# PIC_16F877A_Board_V2.net
KiCad netlist of a schematic drawn in EAGLE
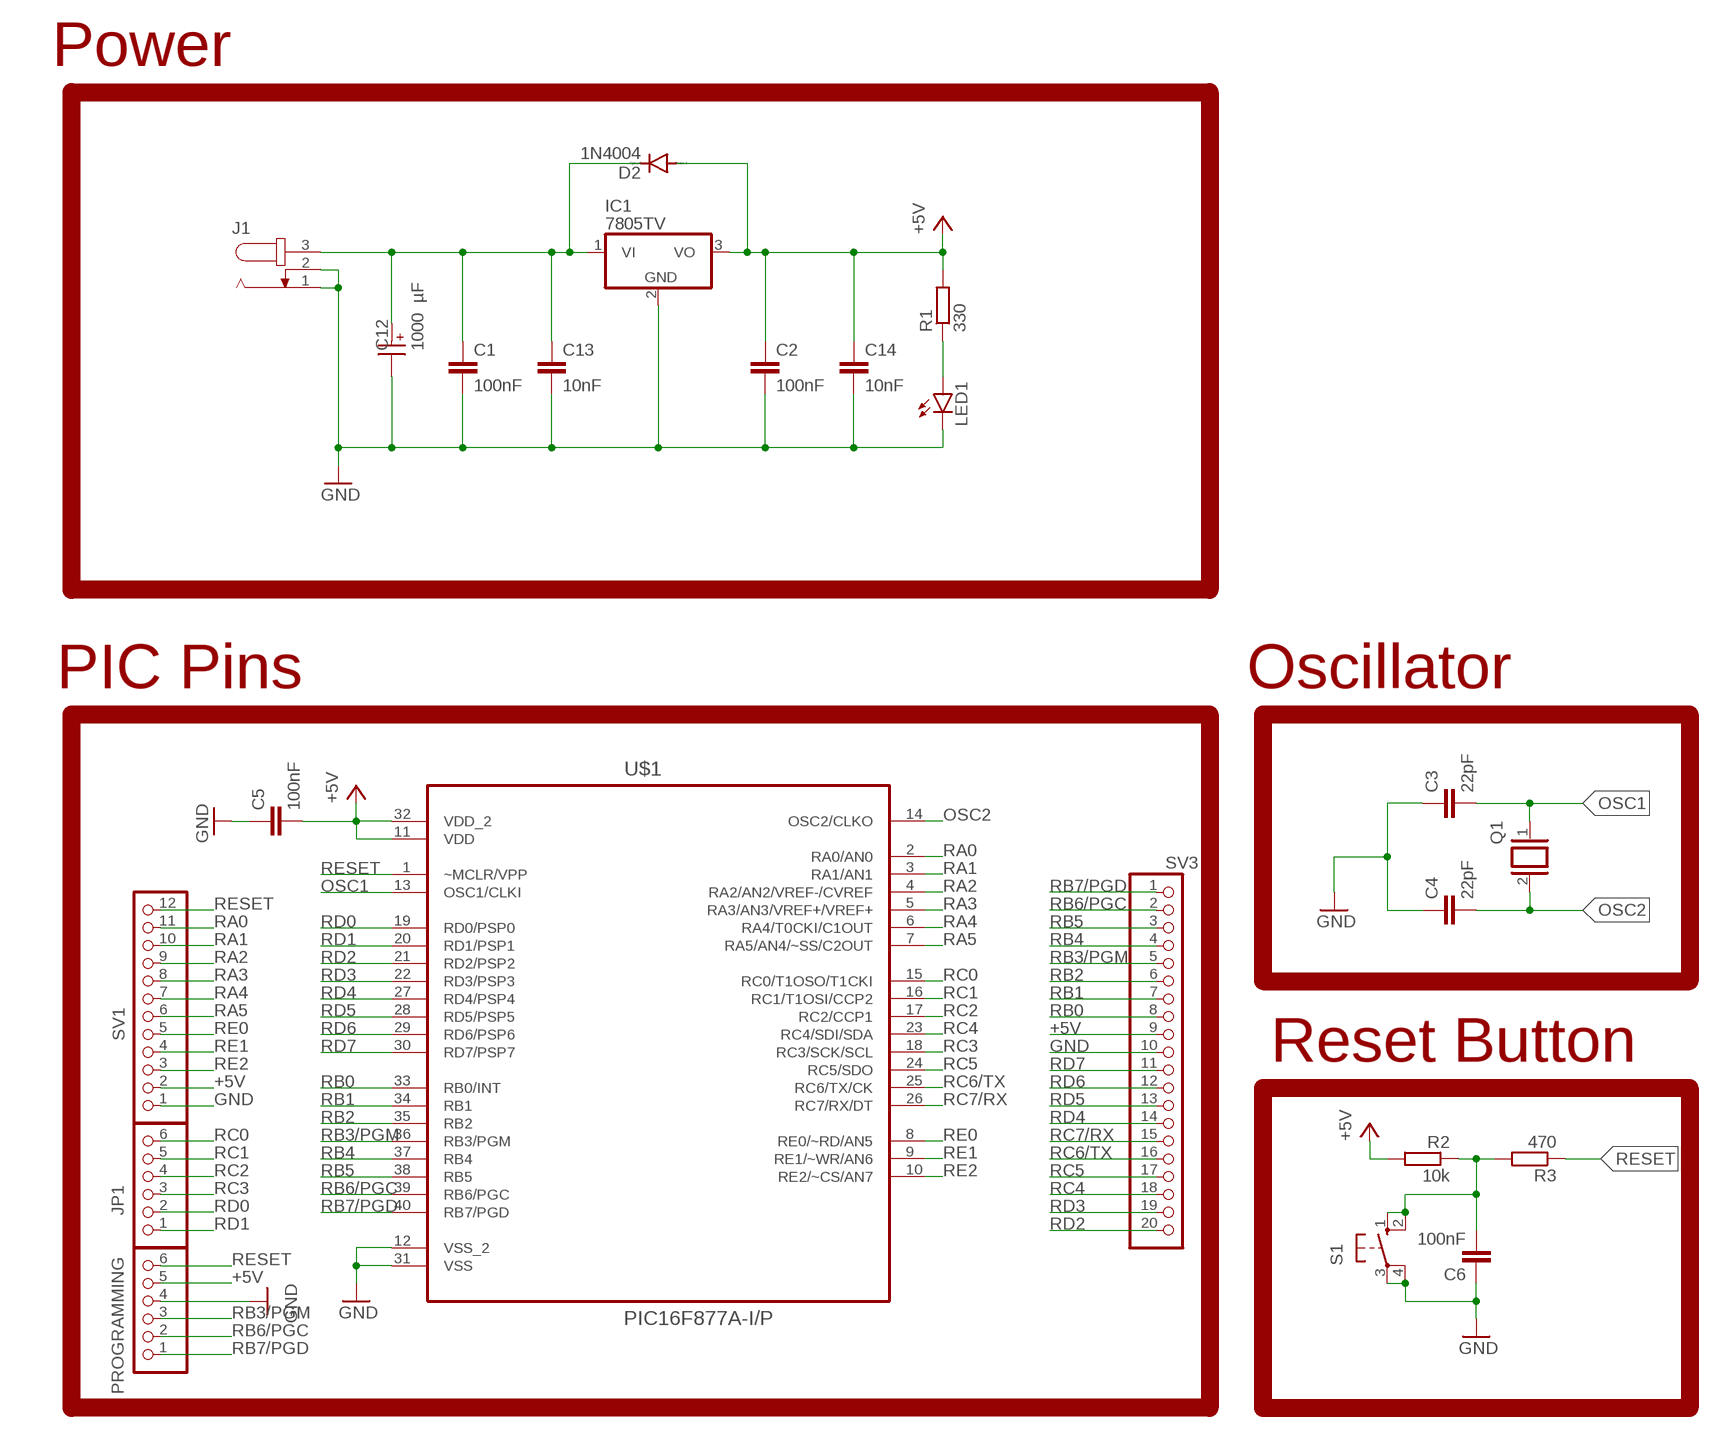
[diagram p0: schematic, sheet 1]

(export (version "E")
  (design (tool "Eeschema 10.0.6"))
  (components
    (comp (ref "C1")
      (value "100nF")
      (footprint "eagle-import:C025-025X050")
      (libsource (lib "eagle-import") (part "C-EU025-025X050"))
    )
    (comp (ref "C2")
      (value "100nF")
      (footprint "eagle-import:C025-025X050")
      (libsource (lib "eagle-import") (part "C-EU025-025X050"))
    )
    (comp (ref "C3")
      (value "22pF")
      (footprint "eagle-import:C025-025X050")
      (libsource (lib "eagle-import") (part "C-EU025-025X050"))
    )
    (comp (ref "C4")
      (value "22pF")
      (footprint "eagle-import:C025-025X050")
      (libsource (lib "eagle-import") (part "C-EU025-025X050"))
    )
    (comp (ref "C5")
      (value "100nF")
      (footprint "eagle-import:C025-025X050")
      (libsource (lib "eagle-import") (part "C-EU025-025X050"))
    )
    (comp (ref "C6")
      (value "100nF")
      (footprint "eagle-import:C025-025X050")
      (libsource (lib "eagle-import") (part "C-EU025-025X050"))
    )
    (comp (ref "C12")
      (value "1000 µF")
      (footprint "eagle-import:WCAP-ATG8_10X12.5(DXL)")
      (libsource (lib "eagle-import") (part "WCAP-ATG8_10X12.5_860010275016"))
    )
    (comp (ref "C13")
      (value "10nF")
      (footprint "eagle-import:C025-025X050")
      (libsource (lib "eagle-import") (part "C-EU025-025X050"))
    )
    (comp (ref "C14")
      (value "10nF")
      (footprint "eagle-import:C025-025X050")
      (libsource (lib "eagle-import") (part "C-EU025-025X050"))
    )
    (comp (ref "D2")
      (value "1N4004")
      (footprint "eagle-import:DO41-10")
      (libsource (lib "eagle-import") (part "1N4004"))
    )
    (comp (ref "IC1")
      (value "7805TV")
      (footprint "eagle-import:TO220V")
      (libsource (lib "eagle-import") (part "78TV05"))
    )
    (comp (ref "J1")
      (value "JACK-PLUG0")
      (footprint "eagle-import:SPC4077")
      (libsource (lib "eagle-import") (part "JACK-PLUG0"))
    )
    (comp (ref "JP1")
      (value "PINHD-1X6")
      (footprint "eagle-import:1X06")
      (libsource (lib "eagle-import") (part "PINHD-1X6"))
    )
    (comp (ref "LED1")
      (value "LED3MM")
      (footprint "eagle-import:LED3MM")
      (libsource (lib "eagle-import") (part "LED3MM"))
    )
    (comp (ref "PROGRAMMING")
      (value "PINHD-1X6")
      (footprint "eagle-import:1X06")
      (libsource (lib "eagle-import") (part "PINHD-1X6"))
    )
    (comp (ref "Q1")
      (value "XTAL/S")
      (footprint "eagle-import:QS")
      (libsource (lib "eagle-import") (part "XTAL/S"))
    )
    (comp (ref "R1")
      (value "330")
      (footprint "eagle-import:0204_7")
      (libsource (lib "eagle-import") (part "R-EU_0204/7"))
    )
    (comp (ref "R2")
      (value "10k")
      (footprint "eagle-import:0204_7")
      (libsource (lib "eagle-import") (part "R-EU_0204/7"))
    )
    (comp (ref "R3")
      (value "470")
      (footprint "eagle-import:0204_7")
      (libsource (lib "eagle-import") (part "R-EU_0204/7"))
    )
    (comp (ref "S1")
      (value "10-XX")
      (footprint "eagle-import:B3F-10XX")
      (fields (field (name "MPN") "B3F-1000"))
      (libsource (lib "eagle-import") (part "10-XX"))
    )
    (comp (ref "SV1")
      (value "PINHD-1X12")
      (footprint "eagle-import:1X12")
      (libsource (lib "eagle-import") (part "PINHD-1X12"))
    )
    (comp (ref "SV3")
      (value "PINHD-1X20")
      (footprint "eagle-import:1X20")
      (libsource (lib "eagle-import") (part "PINHD-1X20"))
    )
    (comp (ref "U$1")
      (value "PIC16F877A-I/P")
      (footprint "eagle-import:16F877A")
      (fields (field (name "MF") "Microchip"))
      (libsource (lib "eagle-import") (part "PIC16F877A-I/P"))
    )
  )
  (nets
    (net (code "1") (name "+5V") (class "Default")
      (node (ref "C14") (pin "1") (pinfunction "1_1") (pintype "passive"))
      (node (ref "C2") (pin "1") (pinfunction "1_1") (pintype "passive"))
      (node (ref "C5") (pin "2") (pinfunction "2_2") (pintype "passive"))
      (node (ref "D2") (pin "A") (pinfunction "A_A") (pintype "passive"))
      (node (ref "IC1") (pin "3") (pinfunction "VO_3") (pintype "passive"))
      (node (ref "PROGRAMMING") (pin "5") (pinfunction "5_5") (pintype "passive"))
      (node (ref "R1") (pin "2") (pinfunction "2_2") (pintype "passive"))
      (node (ref "R2") (pin "2") (pinfunction "2_2") (pintype "passive"))
      (node (ref "SV1") (pin "2") (pinfunction "2_2") (pintype "passive"))
      (node (ref "SV3") (pin "9") (pinfunction "9_9") (pintype "passive"))
      (node (ref "U$1") (pin "11") (pinfunction "VDD_11") (pintype "power_in"))
      (node (ref "U$1") (pin "32") (pinfunction "VDD_2_32") (pintype "power_in"))
    )
    (net (code "2") (name "/RA0") (class "Default")
      (node (ref "SV1") (pin "11") (pinfunction "11_11") (pintype "passive"))
      (node (ref "U$1") (pin "2") (pinfunction "RA0/AN0_2") (pintype "bidirectional"))
    )
    (net (code "3") (name "/RA1") (class "Default")
      (node (ref "SV1") (pin "10") (pinfunction "10_10") (pintype "passive"))
      (node (ref "U$1") (pin "3") (pinfunction "RA1/AN1_3") (pintype "bidirectional"))
    )
    (net (code "4") (name "/RA2") (class "Default")
      (node (ref "SV1") (pin "9") (pinfunction "9_9") (pintype "passive"))
      (node (ref "U$1") (pin "4") (pinfunction "RA2/AN2/VREF-/CVREF_4") (pintype "bidirectional"))
    )
    (net (code "5") (name "/RA3") (class "Default")
      (node (ref "SV1") (pin "8") (pinfunction "8_8") (pintype "passive"))
      (node (ref "U$1") (pin "5") (pinfunction "RA3/AN3/VREF+/VREF+_5") (pintype "bidirectional"))
    )
    (net (code "6") (name "/RA4") (class "Default")
      (node (ref "SV1") (pin "7") (pinfunction "7_7") (pintype "passive"))
      (node (ref "U$1") (pin "6") (pinfunction "RA4/T0CKI/C1OUT_6") (pintype "bidirectional"))
    )
    (net (code "7") (name "/RA5") (class "Default")
      (node (ref "SV1") (pin "6") (pinfunction "6_6") (pintype "passive"))
      (node (ref "U$1") (pin "7") (pinfunction "RA5/AN4/~{SS/C2OUT}_7") (pintype "bidirectional"))
    )
    (net (code "8") (name "/RB0") (class "Default")
      (node (ref "SV3") (pin "8") (pinfunction "8_8") (pintype "passive"))
      (node (ref "U$1") (pin "33") (pinfunction "RB0/INT_33") (pintype "bidirectional"))
    )
    (net (code "9") (name "/RB1") (class "Default")
      (node (ref "SV3") (pin "7") (pinfunction "7_7") (pintype "passive"))
      (node (ref "U$1") (pin "34") (pinfunction "RB1_34") (pintype "bidirectional"))
    )
    (net (code "10") (name "/RB2") (class "Default")
      (node (ref "SV3") (pin "6") (pinfunction "6_6") (pintype "passive"))
      (node (ref "U$1") (pin "35") (pinfunction "RB2_35") (pintype "bidirectional"))
    )
    (net (code "11") (name "/RB3{slash}PGM") (class "Default")
      (node (ref "PROGRAMMING") (pin "3") (pinfunction "3_3") (pintype "passive"))
      (node (ref "SV3") (pin "5") (pinfunction "5_5") (pintype "passive"))
      (node (ref "U$1") (pin "36") (pinfunction "RB3/PGM_36") (pintype "bidirectional"))
    )
    (net (code "12") (name "/RB4") (class "Default")
      (node (ref "SV3") (pin "4") (pinfunction "4_4") (pintype "passive"))
      (node (ref "U$1") (pin "37") (pinfunction "RB4_37") (pintype "bidirectional"))
    )
    (net (code "13") (name "/RB5") (class "Default")
      (node (ref "SV3") (pin "3") (pinfunction "3_3") (pintype "passive"))
      (node (ref "U$1") (pin "38") (pinfunction "RB5_38") (pintype "bidirectional"))
    )
    (net (code "14") (name "/RB6{slash}PGC") (class "Default")
      (node (ref "PROGRAMMING") (pin "2") (pinfunction "2_2") (pintype "passive"))
      (node (ref "SV3") (pin "2") (pinfunction "2_2") (pintype "passive"))
      (node (ref "U$1") (pin "39") (pinfunction "RB6/PGC_39") (pintype "bidirectional"))
    )
    (net (code "15") (name "/RB7{slash}PGD") (class "Default")
      (node (ref "PROGRAMMING") (pin "1") (pinfunction "1_1") (pintype "passive"))
      (node (ref "SV3") (pin "1") (pinfunction "1_1") (pintype "passive"))
      (node (ref "U$1") (pin "40") (pinfunction "RB7/PGD_40") (pintype "bidirectional"))
    )
    (net (code "16") (name "/RC0") (class "Default")
      (node (ref "JP1") (pin "6") (pinfunction "6_6") (pintype "passive"))
      (node (ref "U$1") (pin "15") (pinfunction "RC0/T1OSO/T1CKI_15") (pintype "bidirectional"))
    )
    (net (code "17") (name "/RC1") (class "Default")
      (node (ref "JP1") (pin "5") (pinfunction "5_5") (pintype "passive"))
      (node (ref "U$1") (pin "16") (pinfunction "RC1/T1OSI/CCP2_16") (pintype "bidirectional"))
    )
    (net (code "18") (name "/RC2") (class "Default")
      (node (ref "JP1") (pin "4") (pinfunction "4_4") (pintype "passive"))
      (node (ref "U$1") (pin "17") (pinfunction "RC2/CCP1_17") (pintype "bidirectional"))
    )
    (net (code "19") (name "/RC3") (class "Default")
      (node (ref "JP1") (pin "3") (pinfunction "3_3") (pintype "passive"))
      (node (ref "U$1") (pin "18") (pinfunction "RC3/SCK/SCL_18") (pintype "bidirectional"))
    )
    (net (code "20") (name "/RC4") (class "Default")
      (node (ref "SV3") (pin "18") (pinfunction "18_18") (pintype "passive"))
      (node (ref "U$1") (pin "23") (pinfunction "RC4/SDI/SDA_23") (pintype "bidirectional"))
    )
    (net (code "21") (name "/RC5") (class "Default")
      (node (ref "SV3") (pin "17") (pinfunction "17_17") (pintype "passive"))
      (node (ref "U$1") (pin "24") (pinfunction "RC5/SDO_24") (pintype "bidirectional"))
    )
    (net (code "22") (name "/RC6{slash}TX") (class "Default")
      (node (ref "SV3") (pin "16") (pinfunction "16_16") (pintype "passive"))
      (node (ref "U$1") (pin "25") (pinfunction "RC6/TX/CK_25") (pintype "bidirectional"))
    )
    (net (code "23") (name "/RC7{slash}RX") (class "Default")
      (node (ref "SV3") (pin "15") (pinfunction "15_15") (pintype "passive"))
      (node (ref "U$1") (pin "26") (pinfunction "RC7/RX/DT_26") (pintype "bidirectional"))
    )
    (net (code "24") (name "/RD0") (class "Default")
      (node (ref "JP1") (pin "2") (pinfunction "2_2") (pintype "passive"))
      (node (ref "U$1") (pin "19") (pinfunction "RD0/PSP0_19") (pintype "bidirectional"))
    )
    (net (code "25") (name "/RD1") (class "Default")
      (node (ref "JP1") (pin "1") (pinfunction "1_1") (pintype "passive"))
      (node (ref "U$1") (pin "20") (pinfunction "RD1/PSP1_20") (pintype "bidirectional"))
    )
    (net (code "26") (name "/RD2") (class "Default")
      (node (ref "SV3") (pin "20") (pinfunction "20_20") (pintype "passive"))
      (node (ref "U$1") (pin "21") (pinfunction "RD2/PSP2_21") (pintype "bidirectional"))
    )
    (net (code "27") (name "/RD3") (class "Default")
      (node (ref "SV3") (pin "19") (pinfunction "19_19") (pintype "passive"))
      (node (ref "U$1") (pin "22") (pinfunction "RD3/PSP3_22") (pintype "bidirectional"))
    )
    (net (code "28") (name "/RD4") (class "Default")
      (node (ref "SV3") (pin "14") (pinfunction "14_14") (pintype "passive"))
      (node (ref "U$1") (pin "27") (pinfunction "RD4/PSP4_27") (pintype "bidirectional"))
    )
    (net (code "29") (name "/RD5") (class "Default")
      (node (ref "SV3") (pin "13") (pinfunction "13_13") (pintype "passive"))
      (node (ref "U$1") (pin "28") (pinfunction "RD5/PSP5_28") (pintype "bidirectional"))
    )
    (net (code "30") (name "/RD6") (class "Default")
      (node (ref "SV3") (pin "12") (pinfunction "12_12") (pintype "passive"))
      (node (ref "U$1") (pin "29") (pinfunction "RD6/PSP6_29") (pintype "bidirectional"))
    )
    (net (code "31") (name "/RD7") (class "Default")
      (node (ref "SV3") (pin "11") (pinfunction "11_11") (pintype "passive"))
      (node (ref "U$1") (pin "30") (pinfunction "RD7/PSP7_30") (pintype "bidirectional"))
    )
    (net (code "32") (name "/RE0") (class "Default")
      (node (ref "SV1") (pin "5") (pinfunction "5_5") (pintype "passive"))
      (node (ref "U$1") (pin "8") (pinfunction "RE0/~{RD/AN5}_8") (pintype "bidirectional"))
    )
    (net (code "33") (name "/RE1") (class "Default")
      (node (ref "SV1") (pin "4") (pinfunction "4_4") (pintype "passive"))
      (node (ref "U$1") (pin "9") (pinfunction "RE1/~{WR/AN6}_9") (pintype "bidirectional"))
    )
    (net (code "34") (name "/RE2") (class "Default")
      (node (ref "SV1") (pin "3") (pinfunction "3_3") (pintype "passive"))
      (node (ref "U$1") (pin "10") (pinfunction "RE2/~{CS/AN7}_10") (pintype "bidirectional"))
    )
    (net (code "35") (name "GND") (class "Default")
      (node (ref "C1") (pin "2") (pinfunction "2_2") (pintype "passive"))
      (node (ref "C12") (pin "2") (pinfunction "-_2") (pintype "passive"))
      (node (ref "C13") (pin "2") (pinfunction "2_2") (pintype "passive"))
      (node (ref "C14") (pin "2") (pinfunction "2_2") (pintype "passive"))
      (node (ref "C2") (pin "2") (pinfunction "2_2") (pintype "passive"))
      (node (ref "C3") (pin "1") (pinfunction "1_1") (pintype "passive"))
      (node (ref "C4") (pin "1") (pinfunction "1_1") (pintype "passive"))
      (node (ref "C5") (pin "1") (pinfunction "1_1") (pintype "passive"))
      (node (ref "C6") (pin "1") (pinfunction "1_1") (pintype "passive"))
      (node (ref "IC1") (pin "2") (pinfunction "GND_2") (pintype "passive"))
      (node (ref "J1") (pin "1") (pinfunction "1_1") (pintype "passive"))
      (node (ref "J1") (pin "2") (pinfunction "2_2") (pintype "passive"))
      (node (ref "LED1") (pin "K") (pinfunction "C_K") (pintype "passive"))
      (node (ref "PROGRAMMING") (pin "4") (pinfunction "4_4") (pintype "passive"))
      (node (ref "S1") (pin "3") (pinfunction "P_3") (pintype "passive"))
      (node (ref "S1") (pin "4") (pinfunction "P1_4") (pintype "passive"))
      (node (ref "SV1") (pin "1") (pinfunction "1_1") (pintype "passive"))
      (node (ref "SV3") (pin "10") (pinfunction "10_10") (pintype "passive"))
      (node (ref "U$1") (pin "12") (pinfunction "VSS_2_12") (pintype "power_in"))
      (node (ref "U$1") (pin "31") (pinfunction "VSS_31") (pintype "power_in"))
    )
    (net (code "36") (name "Net-(C12-+)") (class "Default")
      (node (ref "C1") (pin "1") (pinfunction "1_1") (pintype "passive"))
      (node (ref "C12") (pin "1") (pinfunction "+_1") (pintype "passive"))
      (node (ref "C13") (pin "1") (pinfunction "1_1") (pintype "passive"))
      (node (ref "D2") (pin "C") (pinfunction "C_C") (pintype "passive"))
      (node (ref "IC1") (pin "1") (pinfunction "VI_1") (pintype "input"))
      (node (ref "J1") (pin "3") (pinfunction "3_3") (pintype "passive"))
    )
    (net (code "37") (name "Net-(LED1-PadA)") (class "Default")
      (node (ref "LED1") (pin "A") (pinfunction "A_A") (pintype "passive"))
      (node (ref "R1") (pin "1") (pinfunction "1_1") (pintype "passive"))
    )
    (net (code "38") (name "Net-(S1-S)") (class "Default")
      (node (ref "C6") (pin "2") (pinfunction "2_2") (pintype "passive"))
      (node (ref "R2") (pin "1") (pinfunction "1_1") (pintype "passive"))
      (node (ref "R3") (pin "2") (pinfunction "2_2") (pintype "passive"))
      (node (ref "S1") (pin "1") (pinfunction "S_1") (pintype "passive"))
      (node (ref "S1") (pin "2") (pinfunction "S1_2") (pintype "passive"))
    )
    (net (code "39") (name "OSC1") (class "Default")
      (node (ref "C3") (pin "2") (pinfunction "2_2") (pintype "passive"))
      (node (ref "Q1") (pin "1") (pinfunction "1_1") (pintype "passive"))
      (node (ref "U$1") (pin "13") (pinfunction "OSC1/CLKI_13") (pintype "input"))
    )
    (net (code "40") (name "OSC2") (class "Default")
      (node (ref "C4") (pin "2") (pinfunction "2_2") (pintype "passive"))
      (node (ref "Q1") (pin "2") (pinfunction "2_2") (pintype "passive"))
      (node (ref "U$1") (pin "14") (pinfunction "OSC2/CLKO_14") (pintype "output"))
    )
    (net (code "41") (name "RESET") (class "Default")
      (node (ref "PROGRAMMING") (pin "6") (pinfunction "6_6") (pintype "passive"))
      (node (ref "R3") (pin "1") (pinfunction "1_1") (pintype "passive"))
      (node (ref "SV1") (pin "12") (pinfunction "12_12") (pintype "passive"))
      (node (ref "U$1") (pin "1") (pinfunction "~{MCLR/VPP}_1") (pintype "input"))
    )
  )
)
